# mini_backplane.net
KiCad netlist of a schematic drawn in Altium Designer
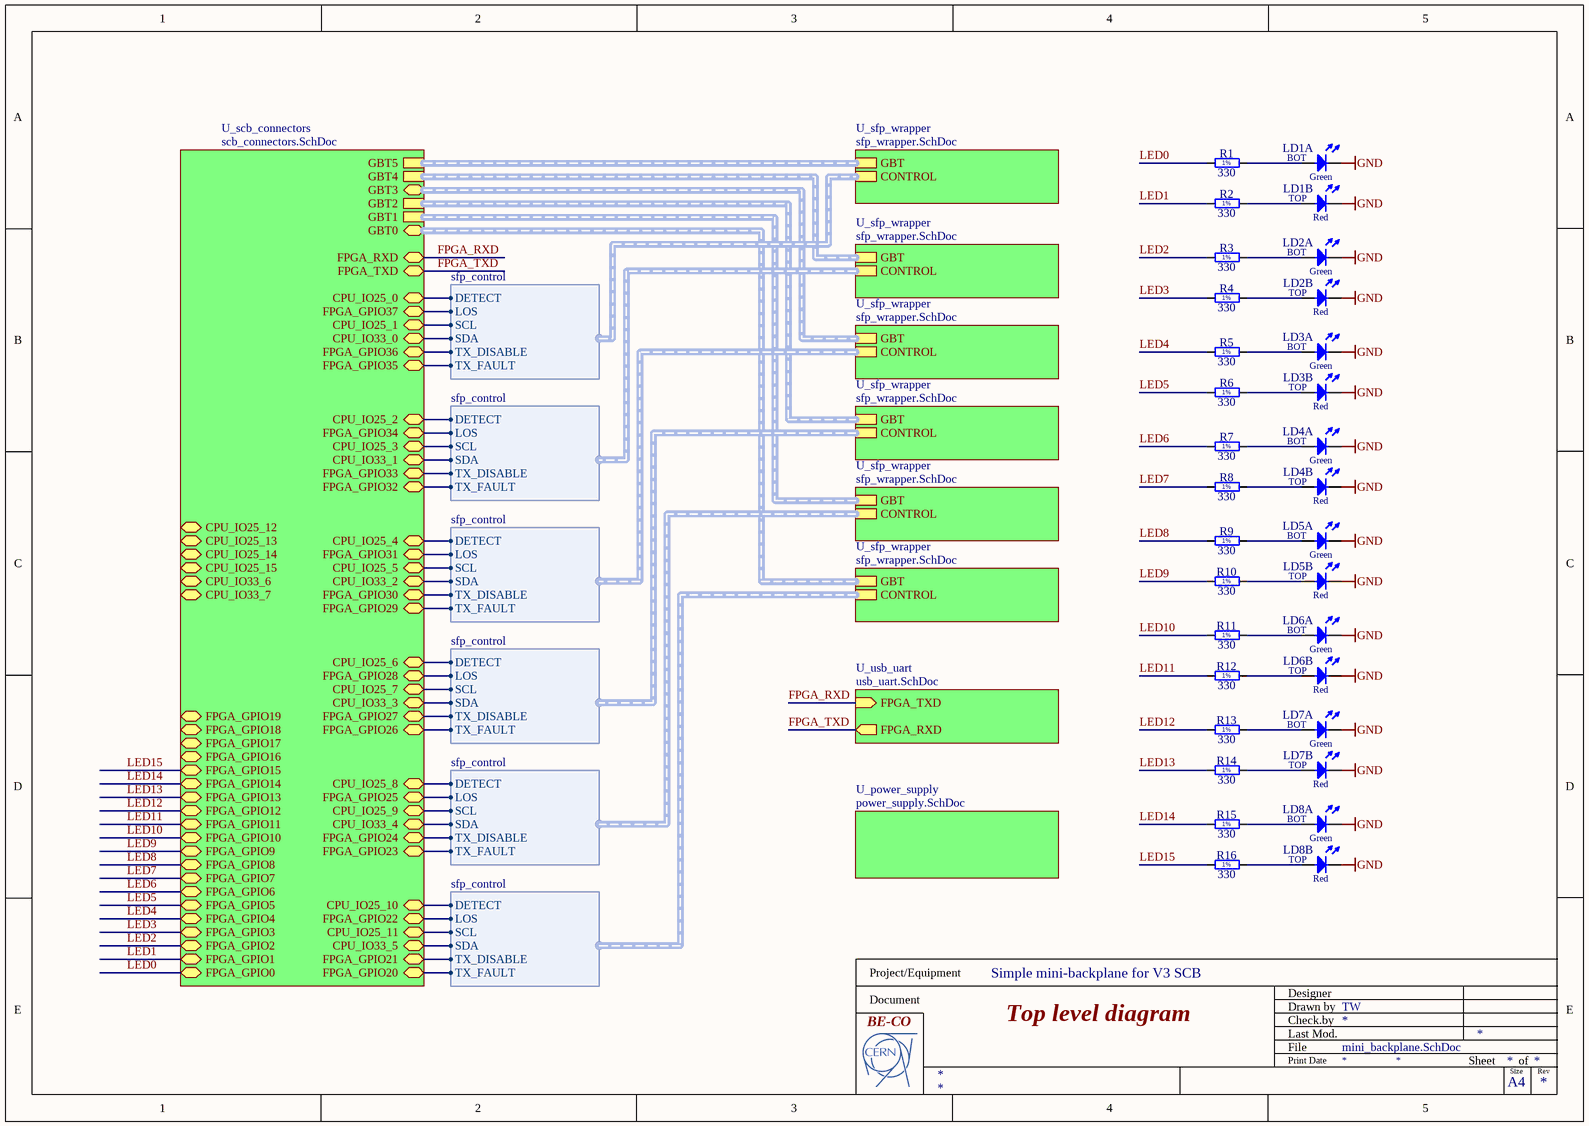
[diagram p0: mini_backplane.SchDoc]

(export (version "E")
  (design (tool "Eeschema 10.0.6"))
  (components
    (comp (ref "LD1")
      (value "Red/Green")
      (footprint "LED_DIALIGHT_571-0112-100F")
      (description "2x LED  Botom Green, Top Red")
      (fields
        (field (name "PART NUMBER") "LED_DIALIGHT_571-0112-100F")
        (field (name "MANUFACTURER") "DIALIGHT")
        (field (name "AUTHOR") "CERN DEM JLC")
      )
      (libsource (lib "ICs And Semiconductors") (part "LED x2 G-1C2A-BOT_R-3C4A-TOP"))
    )
    (comp (ref "LD2")
      (value "Red/Green")
      (footprint "LED_DIALIGHT_571-0112-100F")
      (description "2x LED  Botom Green, Top Red")
      (fields
        (field (name "PART NUMBER") "LED_DIALIGHT_571-0112-100F")
        (field (name "MANUFACTURER") "DIALIGHT")
        (field (name "AUTHOR") "CERN DEM JLC")
      )
      (libsource (lib "ICs And Semiconductors") (part "LED x2 G-1C2A-BOT_R-3C4A-TOP"))
    )
    (comp (ref "LD3")
      (value "Red/Green")
      (footprint "LED_DIALIGHT_571-0112-100F")
      (description "2x LED  Botom Green, Top Red")
      (fields
        (field (name "PART NUMBER") "LED_DIALIGHT_571-0112-100F")
        (field (name "MANUFACTURER") "DIALIGHT")
        (field (name "AUTHOR") "CERN DEM JLC")
      )
      (libsource (lib "ICs And Semiconductors") (part "LED x2 G-1C2A-BOT_R-3C4A-TOP"))
    )
    (comp (ref "LD4")
      (value "Red/Green")
      (footprint "LED_DIALIGHT_571-0112-100F")
      (description "2x LED  Botom Green, Top Red")
      (fields
        (field (name "PART NUMBER") "LED_DIALIGHT_571-0112-100F")
        (field (name "MANUFACTURER") "DIALIGHT")
        (field (name "AUTHOR") "CERN DEM JLC")
      )
      (libsource (lib "ICs And Semiconductors") (part "LED x2 G-1C2A-BOT_R-3C4A-TOP"))
    )
    (comp (ref "LD5")
      (value "Red/Green")
      (footprint "LED_DIALIGHT_571-0112-100F")
      (description "2x LED  Botom Green, Top Red")
      (fields
        (field (name "PART NUMBER") "LED_DIALIGHT_571-0112-100F")
        (field (name "MANUFACTURER") "DIALIGHT")
        (field (name "AUTHOR") "CERN DEM JLC")
      )
      (libsource (lib "ICs And Semiconductors") (part "LED x2 G-1C2A-BOT_R-3C4A-TOP"))
    )
    (comp (ref "LD6")
      (value "Red/Green")
      (footprint "LED_DIALIGHT_571-0112-100F")
      (description "2x LED  Botom Green, Top Red")
      (fields
        (field (name "PART NUMBER") "LED_DIALIGHT_571-0112-100F")
        (field (name "MANUFACTURER") "DIALIGHT")
        (field (name "AUTHOR") "CERN DEM JLC")
      )
      (libsource (lib "ICs And Semiconductors") (part "LED x2 G-1C2A-BOT_R-3C4A-TOP"))
    )
    (comp (ref "LD7")
      (value "Red/Green")
      (footprint "LED_DIALIGHT_571-0112-100F")
      (description "2x LED  Botom Green, Top Red")
      (fields
        (field (name "PART NUMBER") "LED_DIALIGHT_571-0112-100F")
        (field (name "MANUFACTURER") "DIALIGHT")
        (field (name "AUTHOR") "CERN DEM JLC")
      )
      (libsource (lib "ICs And Semiconductors") (part "LED x2 G-1C2A-BOT_R-3C4A-TOP"))
    )
    (comp (ref "LD8")
      (value "Red/Green")
      (footprint "LED_DIALIGHT_571-0112-100F")
      (description "2x LED  Botom Green, Top Red")
      (fields
        (field (name "PART NUMBER") "LED_DIALIGHT_571-0112-100F")
        (field (name "MANUFACTURER") "DIALIGHT")
        (field (name "AUTHOR") "CERN DEM JLC")
      )
      (libsource (lib "ICs And Semiconductors") (part "LED x2 G-1C2A-BOT_R-3C4A-TOP"))
    )
    (comp (ref "R1")
      (value "330")
      (footprint "RESC1608X55N")
      (description "Resistor - 1%")
      (fields
        (field (name "PART NUMBER") "R0603_330R_1%_0.1W_100PPM")
        (field (name "POWER") "0.1W")
        (field (name "AUTHOR") "CERN DEM JLC")
      )
      (libsource (lib "Resistors") (part "Resistor - 1%"))
    )
    (comp (ref "R2")
      (value "330")
      (footprint "RESC1608X55N")
      (description "Resistor - 1%")
      (fields
        (field (name "PART NUMBER") "R0603_330R_1%_0.1W_100PPM")
        (field (name "POWER") "0.1W")
        (field (name "AUTHOR") "CERN DEM JLC")
      )
      (libsource (lib "Resistors") (part "Resistor - 1%"))
    )
    (comp (ref "R3")
      (value "330")
      (footprint "RESC1608X55N")
      (description "Resistor - 1%")
      (fields
        (field (name "PART NUMBER") "R0603_330R_1%_0.1W_100PPM")
        (field (name "POWER") "0.1W")
        (field (name "AUTHOR") "CERN DEM JLC")
      )
      (libsource (lib "Resistors") (part "Resistor - 1%"))
    )
    (comp (ref "R4")
      (value "330")
      (footprint "RESC1608X55N")
      (description "Resistor - 1%")
      (fields
        (field (name "PART NUMBER") "R0603_330R_1%_0.1W_100PPM")
        (field (name "POWER") "0.1W")
        (field (name "AUTHOR") "CERN DEM JLC")
      )
      (libsource (lib "Resistors") (part "Resistor - 1%"))
    )
    (comp (ref "R5")
      (value "330")
      (footprint "RESC1608X55N")
      (description "Resistor - 1%")
      (fields
        (field (name "PART NUMBER") "R0603_330R_1%_0.1W_100PPM")
        (field (name "POWER") "0.1W")
        (field (name "AUTHOR") "CERN DEM JLC")
      )
      (libsource (lib "Resistors") (part "Resistor - 1%"))
    )
    (comp (ref "R6")
      (value "330")
      (footprint "RESC1608X55N")
      (description "Resistor - 1%")
      (fields
        (field (name "PART NUMBER") "R0603_330R_1%_0.1W_100PPM")
        (field (name "POWER") "0.1W")
        (field (name "AUTHOR") "CERN DEM JLC")
      )
      (libsource (lib "Resistors") (part "Resistor - 1%"))
    )
    (comp (ref "R7")
      (value "330")
      (footprint "RESC1608X55N")
      (description "Resistor - 1%")
      (fields
        (field (name "PART NUMBER") "R0603_330R_1%_0.1W_100PPM")
        (field (name "POWER") "0.1W")
        (field (name "AUTHOR") "CERN DEM JLC")
      )
      (libsource (lib "Resistors") (part "Resistor - 1%"))
    )
    (comp (ref "R8")
      (value "330")
      (footprint "RESC1608X55N")
      (description "Resistor - 1%")
      (fields
        (field (name "PART NUMBER") "R0603_330R_1%_0.1W_100PPM")
        (field (name "POWER") "0.1W")
        (field (name "AUTHOR") "CERN DEM JLC")
      )
      (libsource (lib "Resistors") (part "Resistor - 1%"))
    )
    (comp (ref "R9")
      (value "330")
      (footprint "RESC1608X55N")
      (description "Resistor - 1%")
      (fields
        (field (name "PART NUMBER") "R0603_330R_1%_0.1W_100PPM")
        (field (name "POWER") "0.1W")
        (field (name "AUTHOR") "CERN DEM JLC")
      )
      (libsource (lib "Resistors") (part "Resistor - 1%"))
    )
    (comp (ref "R10")
      (value "330")
      (footprint "RESC1608X55N")
      (description "Resistor - 1%")
      (fields
        (field (name "PART NUMBER") "R0603_330R_1%_0.1W_100PPM")
        (field (name "POWER") "0.1W")
        (field (name "AUTHOR") "CERN DEM JLC")
      )
      (libsource (lib "Resistors") (part "Resistor - 1%"))
    )
    (comp (ref "R11")
      (value "330")
      (footprint "RESC1608X55N")
      (description "Resistor - 1%")
      (fields
        (field (name "PART NUMBER") "R0603_330R_1%_0.1W_100PPM")
        (field (name "POWER") "0.1W")
        (field (name "AUTHOR") "CERN DEM JLC")
      )
      (libsource (lib "Resistors") (part "Resistor - 1%"))
    )
    (comp (ref "R12")
      (value "330")
      (footprint "RESC1608X55N")
      (description "Resistor - 1%")
      (fields
        (field (name "PART NUMBER") "R0603_330R_1%_0.1W_100PPM")
        (field (name "POWER") "0.1W")
        (field (name "AUTHOR") "CERN DEM JLC")
      )
      (libsource (lib "Resistors") (part "Resistor - 1%"))
    )
    (comp (ref "R13")
      (value "330")
      (footprint "RESC1608X55N")
      (description "Resistor - 1%")
      (fields
        (field (name "PART NUMBER") "R0603_330R_1%_0.1W_100PPM")
        (field (name "POWER") "0.1W")
        (field (name "AUTHOR") "CERN DEM JLC")
      )
      (libsource (lib "Resistors") (part "Resistor - 1%"))
    )
    (comp (ref "R14")
      (value "330")
      (footprint "RESC1608X55N")
      (description "Resistor - 1%")
      (fields
        (field (name "PART NUMBER") "R0603_330R_1%_0.1W_100PPM")
        (field (name "POWER") "0.1W")
        (field (name "AUTHOR") "CERN DEM JLC")
      )
      (libsource (lib "Resistors") (part "Resistor - 1%"))
    )
    (comp (ref "R15")
      (value "330")
      (footprint "RESC1608X55N")
      (description "Resistor - 1%")
      (fields
        (field (name "PART NUMBER") "R0603_330R_1%_0.1W_100PPM")
        (field (name "POWER") "0.1W")
        (field (name "AUTHOR") "CERN DEM JLC")
      )
      (libsource (lib "Resistors") (part "Resistor - 1%"))
    )
    (comp (ref "R16")
      (value "330")
      (footprint "RESC1608X55N")
      (description "Resistor - 1%")
      (fields
        (field (name "PART NUMBER") "R0603_330R_1%_0.1W_100PPM")
        (field (name "POWER") "0.1W")
        (field (name "AUTHOR") "CERN DEM JLC")
      )
      (libsource (lib "Resistors") (part "Resistor - 1%"))
    )
  )
  (nets
    (net (code "56") (name "/LED0") (class "Default")
      (node (ref "R1") (pin "1") (pinfunction "1_1") (pintype "passive"))
    )
    (net (code "57") (name "/LED1") (class "Default")
      (node (ref "R2") (pin "1") (pinfunction "1_1") (pintype "passive"))
    )
    (net (code "58") (name "/LED2") (class "Default")
      (node (ref "R3") (pin "1") (pinfunction "1_1") (pintype "passive"))
    )
    (net (code "59") (name "/LED3") (class "Default")
      (node (ref "R4") (pin "1") (pinfunction "1_1") (pintype "passive"))
    )
    (net (code "60") (name "/LED4") (class "Default")
      (node (ref "R5") (pin "1") (pinfunction "1_1") (pintype "passive"))
    )
    (net (code "61") (name "/LED5") (class "Default")
      (node (ref "R6") (pin "1") (pinfunction "1_1") (pintype "passive"))
    )
    (net (code "62") (name "/LED6") (class "Default")
      (node (ref "R7") (pin "1") (pinfunction "1_1") (pintype "passive"))
    )
    (net (code "63") (name "/LED7") (class "Default")
      (node (ref "R8") (pin "1") (pinfunction "1_1") (pintype "passive"))
    )
    (net (code "64") (name "/LED8") (class "Default")
      (node (ref "R9") (pin "1") (pinfunction "1_1") (pintype "passive"))
    )
    (net (code "65") (name "/LED9") (class "Default")
      (node (ref "R10") (pin "1") (pinfunction "1_1") (pintype "passive"))
    )
    (net (code "66") (name "/LED10") (class "Default")
      (node (ref "R11") (pin "1") (pinfunction "1_1") (pintype "passive"))
    )
    (net (code "67") (name "/LED11") (class "Default")
      (node (ref "R12") (pin "1") (pinfunction "1_1") (pintype "passive"))
    )
    (net (code "68") (name "/LED12") (class "Default")
      (node (ref "R13") (pin "1") (pinfunction "1_1") (pintype "passive"))
    )
    (net (code "69") (name "/LED13") (class "Default")
      (node (ref "R14") (pin "1") (pinfunction "1_1") (pintype "passive"))
    )
    (net (code "70") (name "/LED14") (class "Default")
      (node (ref "R15") (pin "1") (pinfunction "1_1") (pintype "passive"))
    )
    (net (code "71") (name "/LED15") (class "Default")
      (node (ref "R16") (pin "1") (pinfunction "1_1") (pintype "passive"))
    )
    (net (code "73") (name "GND") (class "Default")
      (node (ref "LD1") (pin "1") (pinfunction "C_1") (pintype "passive"))
      (node (ref "LD1") (pin "3") (pinfunction "C_3") (pintype "passive"))
      (node (ref "LD2") (pin "1") (pinfunction "C_1") (pintype "passive"))
      (node (ref "LD2") (pin "3") (pinfunction "C_3") (pintype "passive"))
      (node (ref "LD3") (pin "1") (pinfunction "C_1") (pintype "passive"))
      (node (ref "LD3") (pin "3") (pinfunction "C_3") (pintype "passive"))
      (node (ref "LD4") (pin "1") (pinfunction "C_1") (pintype "passive"))
      (node (ref "LD4") (pin "3") (pinfunction "C_3") (pintype "passive"))
      (node (ref "LD5") (pin "1") (pinfunction "C_1") (pintype "passive"))
      (node (ref "LD5") (pin "3") (pinfunction "C_3") (pintype "passive"))
      (node (ref "LD6") (pin "1") (pinfunction "C_1") (pintype "passive"))
      (node (ref "LD6") (pin "3") (pinfunction "C_3") (pintype "passive"))
      (node (ref "LD7") (pin "1") (pinfunction "C_1") (pintype "passive"))
      (node (ref "LD7") (pin "3") (pinfunction "C_3") (pintype "passive"))
      (node (ref "LD8") (pin "1") (pinfunction "C_1") (pintype "passive"))
      (node (ref "LD8") (pin "3") (pinfunction "C_3") (pintype "passive"))
    )
    (net (code "74") (name "Net-(LD1A-A)") (class "Default")
      (node (ref "LD1") (pin "2") (pinfunction "A_2") (pintype "passive"))
      (node (ref "R1") (pin "2") (pinfunction "2_2") (pintype "passive"))
    )
    (net (code "75") (name "Net-(LD1B-A)") (class "Default")
      (node (ref "LD1") (pin "4") (pinfunction "A_4") (pintype "passive"))
      (node (ref "R2") (pin "2") (pinfunction "2_2") (pintype "passive"))
    )
    (net (code "76") (name "Net-(LD2A-A)") (class "Default")
      (node (ref "LD2") (pin "2") (pinfunction "A_2") (pintype "passive"))
      (node (ref "R3") (pin "2") (pinfunction "2_2") (pintype "passive"))
    )
    (net (code "77") (name "Net-(LD2B-A)") (class "Default")
      (node (ref "LD2") (pin "4") (pinfunction "A_4") (pintype "passive"))
      (node (ref "R4") (pin "2") (pinfunction "2_2") (pintype "passive"))
    )
    (net (code "78") (name "Net-(LD3A-A)") (class "Default")
      (node (ref "LD3") (pin "2") (pinfunction "A_2") (pintype "passive"))
      (node (ref "R5") (pin "2") (pinfunction "2_2") (pintype "passive"))
    )
    (net (code "79") (name "Net-(LD3B-A)") (class "Default")
      (node (ref "LD3") (pin "4") (pinfunction "A_4") (pintype "passive"))
      (node (ref "R6") (pin "2") (pinfunction "2_2") (pintype "passive"))
    )
    (net (code "80") (name "Net-(LD4A-A)") (class "Default")
      (node (ref "LD4") (pin "2") (pinfunction "A_2") (pintype "passive"))
      (node (ref "R7") (pin "2") (pinfunction "2_2") (pintype "passive"))
    )
    (net (code "81") (name "Net-(LD4B-A)") (class "Default")
      (node (ref "LD4") (pin "4") (pinfunction "A_4") (pintype "passive"))
      (node (ref "R8") (pin "2") (pinfunction "2_2") (pintype "passive"))
    )
    (net (code "82") (name "Net-(LD5A-A)") (class "Default")
      (node (ref "LD5") (pin "2") (pinfunction "A_2") (pintype "passive"))
      (node (ref "R9") (pin "2") (pinfunction "2_2") (pintype "passive"))
    )
    (net (code "83") (name "Net-(LD5B-A)") (class "Default")
      (node (ref "LD5") (pin "4") (pinfunction "A_4") (pintype "passive"))
      (node (ref "R10") (pin "2") (pinfunction "2_2") (pintype "passive"))
    )
    (net (code "84") (name "Net-(LD6A-A)") (class "Default")
      (node (ref "LD6") (pin "2") (pinfunction "A_2") (pintype "passive"))
      (node (ref "R11") (pin "2") (pinfunction "2_2") (pintype "passive"))
    )
    (net (code "85") (name "Net-(LD6B-A)") (class "Default")
      (node (ref "LD6") (pin "4") (pinfunction "A_4") (pintype "passive"))
      (node (ref "R12") (pin "2") (pinfunction "2_2") (pintype "passive"))
    )
    (net (code "86") (name "Net-(LD7A-A)") (class "Default")
      (node (ref "LD7") (pin "2") (pinfunction "A_2") (pintype "passive"))
      (node (ref "R13") (pin "2") (pinfunction "2_2") (pintype "passive"))
    )
    (net (code "87") (name "Net-(LD7B-A)") (class "Default")
      (node (ref "LD7") (pin "4") (pinfunction "A_4") (pintype "passive"))
      (node (ref "R14") (pin "2") (pinfunction "2_2") (pintype "passive"))
    )
    (net (code "88") (name "Net-(LD8A-A)") (class "Default")
      (node (ref "LD8") (pin "2") (pinfunction "A_2") (pintype "passive"))
      (node (ref "R15") (pin "2") (pinfunction "2_2") (pintype "passive"))
    )
    (net (code "89") (name "Net-(LD8B-A)") (class "Default")
      (node (ref "LD8") (pin "4") (pinfunction "A_4") (pintype "passive"))
      (node (ref "R16") (pin "2") (pinfunction "2_2") (pintype "passive"))
    )
  )
)
